# FPGA_CONFIG.net
KiCad netlist of a schematic drawn in Altium Designer
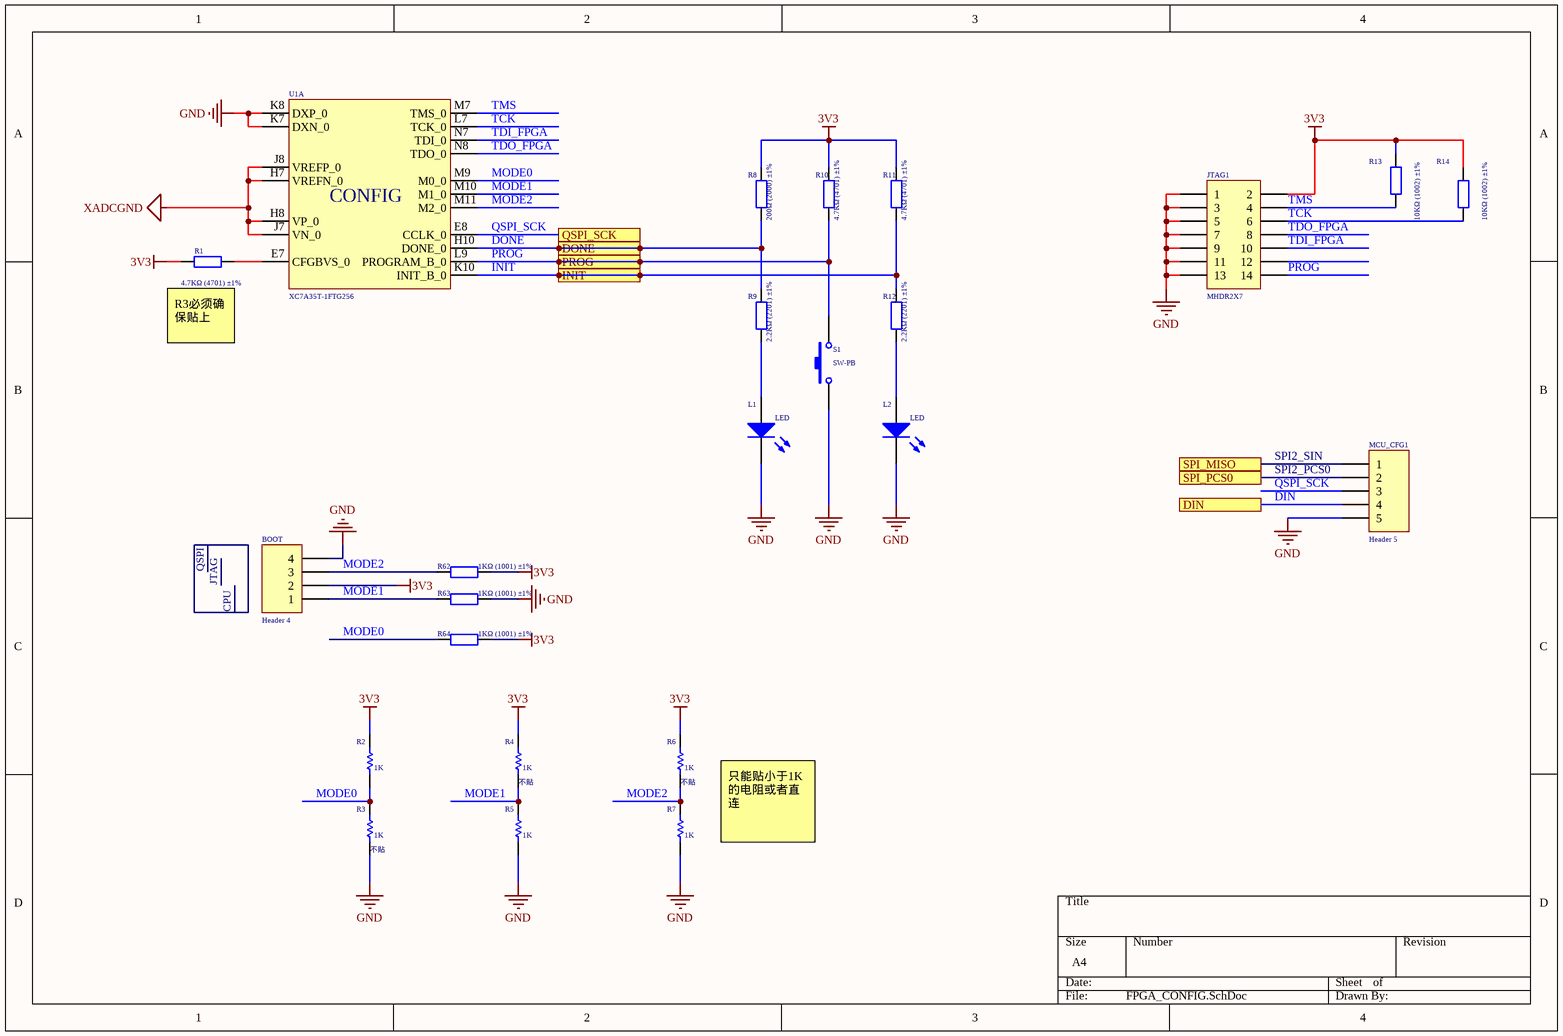
[diagram p0: FPGA_CONFIG.SchDoc]

(export (version "E")
  (design (tool "Eeschema 10.0.6"))
  (components
    (comp (ref "BOOT")
      (value "Header 4")
      (footprint "HDR1X4")
      (description "Header, 4-Pin")
      (fields (field (name "PUBLISHER") "Altium Limited"))
      (libsource (lib "Sparks") (part "Header 4"))
    )
    (comp (ref "JTAG1")
      (value "MHDR2X7")
      (footprint "SMT7*2-2MM")
      (description "Header, 7-Pin, Dual row")
      (fields (field (name "PUBLISHER") "Altium Limited"))
      (libsource (lib "Miscellaneous Connectors") (part "MHDR2X7"))
    )
    (comp (ref "L1") (value "LED") (footprint "1608[0603]") (libsource (lib "Sparks") (part "LED")))
    (comp (ref "L2") (value "LED") (footprint "1608[0603]") (libsource (lib "Sparks") (part "LED")))
    (comp (ref "MCU_CFG1")
      (value "Header 5")
      (footprint "MHDR1X5")
      (description "Header, 5-Pin")
      (fields (field (name "PUBLISHER") "Altium Limited"))
      (libsource (lib "Sparks") (part "Header 5"))
    )
    (comp (ref "R1")
      (value "4.7KΩ (4701) ±1%")
      (footprint "0402_R")
      (description "贴片电阻")
      (libsource (lib "") (part "0402 4.7KΩ (4701) 1%_1"))
    )
    (comp (ref "R2")
      (value "1K")
      (footprint "1608[0603]")
      (description "贴片电阻")
      (fields (field (name "Comment") "Res") (field (name "PUBLISHER") "Altium Limited"))
      (libsource (lib "Sparks") (part "Res"))
    )
    (comp (ref "R3")
      (value "不贴")
      (footprint "1608[0603]")
      (description "贴片电阻")
      (fields (field (name "ALTIUM_VALUE") "1K") (field (name "PUBLISHER") "Altium Limited"))
      (libsource (lib "Sparks") (part "Res"))
    )
    (comp (ref "R4")
      (value "不贴")
      (footprint "1608[0603]")
      (description "贴片电阻")
      (fields (field (name "ALTIUM_VALUE") "1K") (field (name "PUBLISHER") "Altium Limited"))
      (libsource (lib "Sparks") (part "Res"))
    )
    (comp (ref "R5")
      (value "1K")
      (footprint "1608[0603]")
      (description "贴片电阻")
      (fields (field (name "Comment") "Res") (field (name "PUBLISHER") "Altium Limited"))
      (libsource (lib "Sparks") (part "Res"))
    )
    (comp (ref "R6")
      (value "不贴")
      (footprint "1608[0603]")
      (description "贴片电阻")
      (fields (field (name "ALTIUM_VALUE") "1K") (field (name "PUBLISHER") "Altium Limited"))
      (libsource (lib "Sparks") (part "Res"))
    )
    (comp (ref "R7")
      (value "1K")
      (footprint "1608[0603]")
      (description "贴片电阻")
      (fields (field (name "Comment") "Res") (field (name "PUBLISHER") "Altium Limited"))
      (libsource (lib "Sparks") (part "Res"))
    )
    (comp (ref "R8")
      (value "200Ω (2000) ±1%")
      (footprint "0402_R")
      (description "贴片电阻")
      (libsource (lib "RES") (part "0402 200Ω (2000) 1%"))
    )
    (comp (ref "R9")
      (value "2.2KΩ (2201) ±1%")
      (footprint "0402_R")
      (description "贴片电阻")
      (libsource (lib "Miscellaneous Devices LC") (part "0402 2.2KΩ (2201) 1%"))
    )
    (comp (ref "R10")
      (value "4.7KΩ (4701) ±1%")
      (footprint "0402_R")
      (description "贴片电阻")
      (libsource (lib "RES") (part "0402 4.7KΩ (4701) 1%"))
    )
    (comp (ref "R11")
      (value "4.7KΩ (4701) ±1%")
      (footprint "0402_R")
      (description "贴片电阻")
      (libsource (lib "RES") (part "0402 4.7KΩ (4701) 1%"))
    )
    (comp (ref "R12")
      (value "2.2KΩ (2201) ±1%")
      (footprint "0402_R")
      (description "贴片电阻")
      (libsource (lib "Miscellaneous Devices LC") (part "0402 2.2KΩ (2201) 1%"))
    )
    (comp (ref "R13")
      (value "10KΩ (1002) ±1%")
      (footprint "0402_R")
      (description "贴片电阻")
      (libsource (lib "RES") (part "0402 10KΩ (1002) 1%"))
    )
    (comp (ref "R14")
      (value "10KΩ (1002) ±1%")
      (footprint "0402_R")
      (description "贴片电阻")
      (libsource (lib "RES") (part "0402 10KΩ (1002) 1%"))
    )
    (comp (ref "R62")
      (value "1KΩ (1001) ±1%")
      (footprint "0402_R")
      (description "贴片电阻")
      (libsource (lib "Miscellaneous Devices LC") (part "0402 1KΩ (1001) 1%"))
    )
    (comp (ref "R63")
      (value "1KΩ (1001) ±1%")
      (footprint "0402_R")
      (description "贴片电阻")
      (libsource (lib "Miscellaneous Devices LC") (part "0402 1KΩ (1001) 1%"))
    )
    (comp (ref "R64")
      (value "1KΩ (1001) ±1%")
      (footprint "0402_R")
      (description "贴片电阻")
      (libsource (lib "Miscellaneous Devices LC") (part "0402 1KΩ (1001) 1%"))
    )
    (comp (ref "S1")
      (value "SW-PB")
      (footprint "key 3*4*2")
      (description "Switch")
      (fields (field (name "PUBLISHER") "Altium Limited"))
      (libsource (lib "Miscellaneous Devices") (part "SW-PB"))
    )
    (comp (ref "U1")
      (value "XC7A35T-1FTG256")
      (footprint "BGA100P9X9-81A")
      (libsource (lib "Schlib") (part "XC7A35T-1FTG256"))
    )
  )
  (nets
    (net (code "1") (name "/DIN") (class "Default")
      (node (ref "MCU_CFG1") (pin "4") (pinfunction "4_4") (pintype "passive"))
    )
    (net (code "2") (name "/DONE") (class "Default")
      (node (ref "R8") (pin "1") (pinfunction "1_1") (pintype "passive"))
      (node (ref "R9") (pin "2") (pinfunction "2_2") (pintype "passive"))
      (node (ref "U1") (pin "H10") (pinfunction "DONE_0_H10") (pintype "passive"))
    )
    (net (code "3") (name "/INIT") (class "Default")
      (node (ref "R11") (pin "1") (pinfunction "1_1") (pintype "passive"))
      (node (ref "R12") (pin "2") (pinfunction "2_2") (pintype "passive"))
      (node (ref "U1") (pin "K10") (pinfunction "INIT_B_0_K10") (pintype "passive"))
    )
    (net (code "4") (name "/MODE0") (class "Default")
      (node (ref "R2") (pin "1") (pinfunction "1_1") (pintype "passive"))
      (node (ref "R3") (pin "2") (pinfunction "2_2") (pintype "passive"))
      (node (ref "R64") (pin "1") (pinfunction "1_1") (pintype "passive"))
      (node (ref "U1") (pin "M9") (pinfunction "M0_0_M9") (pintype "passive"))
    )
    (net (code "5") (name "/MODE1") (class "Default")
      (node (ref "BOOT") (pin "1") (pinfunction "1_1") (pintype "passive"))
      (node (ref "R4") (pin "1") (pinfunction "1_1") (pintype "passive"))
      (node (ref "R5") (pin "2") (pinfunction "2_2") (pintype "passive"))
      (node (ref "R63") (pin "1") (pinfunction "1_1") (pintype "passive"))
      (node (ref "U1") (pin "M10") (pinfunction "M1_0_M10") (pintype "passive"))
    )
    (net (code "6") (name "/MODE2") (class "Default")
      (node (ref "BOOT") (pin "3") (pinfunction "3_3") (pintype "passive"))
      (node (ref "R6") (pin "1") (pinfunction "1_1") (pintype "passive"))
      (node (ref "R62") (pin "1") (pinfunction "1_1") (pintype "passive"))
      (node (ref "R7") (pin "2") (pinfunction "2_2") (pintype "passive"))
      (node (ref "U1") (pin "M11") (pinfunction "M2_0_M11") (pintype "passive"))
    )
    (net (code "7") (name "/PROG") (class "Default")
      (node (ref "JTAG1") (pin "14") (pinfunction "14_14") (pintype "passive"))
      (node (ref "R10") (pin "1") (pinfunction "1_1") (pintype "passive"))
      (node (ref "S1") (pin "2") (pinfunction "2_2") (pintype "passive"))
      (node (ref "U1") (pin "L9") (pinfunction "PROGRAM_B_0_L9") (pintype "passive"))
    )
    (net (code "8") (name "/QSPI_SCK") (class "Default")
      (node (ref "MCU_CFG1") (pin "3") (pinfunction "3_3") (pintype "passive"))
      (node (ref "U1") (pin "E8") (pinfunction "CCLK_0_E8") (pintype "passive"))
    )
    (net (code "9") (name "/SPI2_PCS0") (class "Default")
      (node (ref "MCU_CFG1") (pin "2") (pinfunction "2_2") (pintype "passive"))
    )
    (net (code "10") (name "/SPI2_SIN") (class "Default")
      (node (ref "MCU_CFG1") (pin "1") (pinfunction "1_1") (pintype "passive"))
    )
    (net (code "11") (name "/TCK") (class "Default")
      (node (ref "JTAG1") (pin "6") (pinfunction "6_6") (pintype "passive"))
      (node (ref "R14") (pin "1") (pinfunction "1_1") (pintype "passive"))
      (node (ref "U1") (pin "L7") (pinfunction "TCK_0_L7") (pintype "passive"))
    )
    (net (code "12") (name "/TDI_FPGA") (class "Default")
      (node (ref "JTAG1") (pin "10") (pinfunction "10_10") (pintype "passive"))
      (node (ref "U1") (pin "N7") (pinfunction "TDI_0_N7") (pintype "passive"))
    )
    (net (code "13") (name "/TDO_FPGA") (class "Default")
      (node (ref "JTAG1") (pin "8") (pinfunction "8_8") (pintype "passive"))
      (node (ref "U1") (pin "N8") (pinfunction "TDO_0_N8") (pintype "passive"))
    )
    (net (code "14") (name "/TMS") (class "Default")
      (node (ref "JTAG1") (pin "4") (pinfunction "4_4") (pintype "passive"))
      (node (ref "R13") (pin "1") (pinfunction "1_1") (pintype "passive"))
      (node (ref "U1") (pin "M7") (pinfunction "TMS_0_M7") (pintype "passive"))
    )
    (net (code "15") (name "3V3") (class "Default")
      (node (ref "BOOT") (pin "2") (pinfunction "2_2") (pintype "passive"))
      (node (ref "JTAG1") (pin "2") (pinfunction "2_2") (pintype "passive"))
      (node (ref "R1") (pin "1") (pinfunction "1_1") (pintype "passive"))
      (node (ref "R10") (pin "2") (pinfunction "2_2") (pintype "passive"))
      (node (ref "R11") (pin "2") (pinfunction "2_2") (pintype "passive"))
      (node (ref "R13") (pin "2") (pinfunction "2_2") (pintype "passive"))
      (node (ref "R14") (pin "2") (pinfunction "2_2") (pintype "passive"))
      (node (ref "R2") (pin "2") (pinfunction "2_2") (pintype "passive"))
      (node (ref "R4") (pin "2") (pinfunction "2_2") (pintype "passive"))
      (node (ref "R6") (pin "2") (pinfunction "2_2") (pintype "passive"))
      (node (ref "R62") (pin "2") (pinfunction "2_2") (pintype "passive"))
      (node (ref "R64") (pin "2") (pinfunction "2_2") (pintype "passive"))
      (node (ref "R8") (pin "2") (pinfunction "2_2") (pintype "passive"))
    )
    (net (code "16") (name "GND") (class "Default")
      (node (ref "BOOT") (pin "4") (pinfunction "4_4") (pintype "passive"))
      (node (ref "JTAG1") (pin "1") (pinfunction "1_1") (pintype "passive"))
      (node (ref "JTAG1") (pin "11") (pinfunction "11_11") (pintype "passive"))
      (node (ref "JTAG1") (pin "13") (pinfunction "13_13") (pintype "passive"))
      (node (ref "JTAG1") (pin "3") (pinfunction "3_3") (pintype "passive"))
      (node (ref "JTAG1") (pin "5") (pinfunction "5_5") (pintype "passive"))
      (node (ref "JTAG1") (pin "7") (pinfunction "7_7") (pintype "passive"))
      (node (ref "JTAG1") (pin "9") (pinfunction "9_9") (pintype "passive"))
      (node (ref "L1") (pin "2") (pinfunction "K_2") (pintype "passive"))
      (node (ref "L2") (pin "2") (pinfunction "K_2") (pintype "passive"))
      (node (ref "MCU_CFG1") (pin "5") (pinfunction "5_5") (pintype "passive"))
      (node (ref "R3") (pin "1") (pinfunction "1_1") (pintype "passive"))
      (node (ref "R5") (pin "1") (pinfunction "1_1") (pintype "passive"))
      (node (ref "R63") (pin "2") (pinfunction "2_2") (pintype "passive"))
      (node (ref "R7") (pin "1") (pinfunction "1_1") (pintype "passive"))
      (node (ref "S1") (pin "1") (pinfunction "1_1") (pintype "passive"))
      (node (ref "U1") (pin "K7") (pinfunction "DXN_0_K7") (pintype "passive"))
      (node (ref "U1") (pin "K8") (pinfunction "DXP_0_K8") (pintype "passive"))
    )
    (net (code "17") (name "Net-(L1-A)") (class "Default")
      (node (ref "L1") (pin "1") (pinfunction "A_1") (pintype "passive"))
      (node (ref "R9") (pin "1") (pinfunction "1_1") (pintype "passive"))
    )
    (net (code "18") (name "Net-(L2-A)") (class "Default")
      (node (ref "L2") (pin "1") (pinfunction "A_1") (pintype "passive"))
      (node (ref "R12") (pin "1") (pinfunction "1_1") (pintype "passive"))
    )
    (net (code "19") (name "Net-(U1A-CFGBVS_0)") (class "Default")
      (node (ref "R1") (pin "2") (pinfunction "2_2") (pintype "passive"))
      (node (ref "U1") (pin "E7") (pinfunction "CFGBVS_0_E7") (pintype "passive"))
    )
    (net (code "20") (name "XADCGND") (class "Default")
      (node (ref "U1") (pin "H7") (pinfunction "VREFN_0_H7") (pintype "passive"))
      (node (ref "U1") (pin "H8") (pinfunction "VP_0_H8") (pintype "passive"))
      (node (ref "U1") (pin "J7") (pinfunction "VN_0_J7") (pintype "passive"))
      (node (ref "U1") (pin "J8") (pinfunction "VREFP_0_J8") (pintype "passive"))
    )
    (net (code "21") (name "unconnected-(JTAG1-Pad12)") (class "Default")
      (node (ref "JTAG1") (pin "12") (pinfunction "12_12") (pintype "passive"))
    )
  )
)
